# Main_Power.net
KiCad netlist of a schematic drawn in Altium Designer
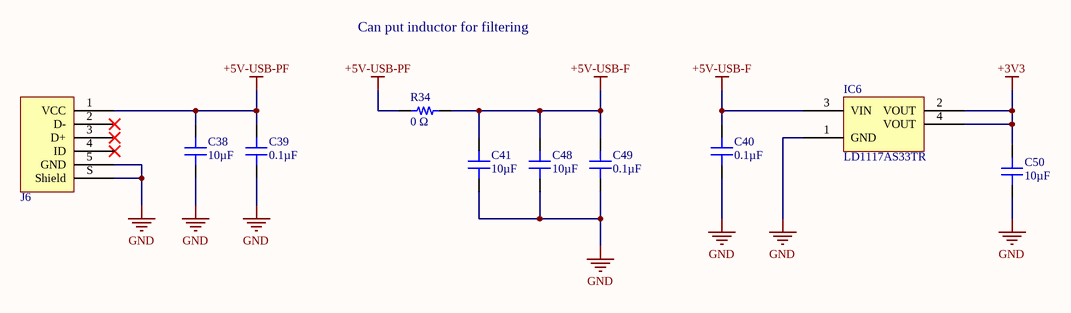
[diagram p0: Main Power.SchDoc]

(export (version "E")
  (design (tool "Eeschema 10.0.6"))
  (components
    (comp (ref "C38")
      (value "10µF")
      (footprint "CAP 0805_2012")
      (description "CAP CER 10UF 6.3V X5R 0805")
      (fields (field (name "PART NUMBER") "08056D106KAT4A") (field (name "MANUFACTURER") "AVX Corporation"))
      (libsource (lib "Generic Altium Database") (part "Capacitor"))
    )
    (comp (ref "C39")
      (value "0.1µF")
      (footprint "CAP 0402_1005")
      (description "CAP CER 0.1UF 6.3V X7R 0402")
      (fields
        (field (name "PART NUMBER") "0402B104K6R3CT")
        (field (name "MANUFACTURER") "Walsin Technology Corporation")
      )
      (libsource (lib "Generic Altium Database") (part "Capacitor"))
    )
    (comp (ref "C40")
      (value "0.1µF")
      (footprint "CAP 0402_1005")
      (description "CAP CER 0.1UF 6.3V X7R 0402")
      (fields
        (field (name "PART NUMBER") "0402B104K6R3CT")
        (field (name "MANUFACTURER") "Walsin Technology Corporation")
      )
      (libsource (lib "Generic Altium Database") (part "Capacitor"))
    )
    (comp (ref "C41")
      (value "10µF")
      (footprint "CAP 0805_2012")
      (description "CAP CER 10UF 6.3V X5R 0805")
      (fields (field (name "PART NUMBER") "08056D106KAT4A") (field (name "MANUFACTURER") "AVX Corporation"))
      (libsource (lib "Generic Altium Database") (part "Capacitor"))
    )
    (comp (ref "C48")
      (value "10µF")
      (footprint "CAP 0805_2012")
      (description "CAP CER 10UF 6.3V X5R 0805")
      (fields (field (name "PART NUMBER") "08056D106KAT4A") (field (name "MANUFACTURER") "AVX Corporation"))
      (libsource (lib "Generic Altium Database") (part "Capacitor"))
    )
    (comp (ref "C49")
      (value "0.1µF")
      (footprint "CAP 0402_1005")
      (description "CAP CER 0.1UF 6.3V X7R 0402")
      (fields
        (field (name "PART NUMBER") "0402B104K6R3CT")
        (field (name "MANUFACTURER") "Walsin Technology Corporation")
      )
      (libsource (lib "Generic Altium Database") (part "Capacitor"))
    )
    (comp (ref "C50")
      (value "10µF")
      (footprint "CAP 0805_2012")
      (description "CAP CER 10UF 6.3V X5R 0805")
      (fields (field (name "PART NUMBER") "08056D106KAT4A") (field (name "MANUFACTURER") "AVX Corporation"))
      (libsource (lib "Generic Altium Database") (part "Capacitor"))
    )
    (comp (ref "IC6")
      (value "LD1117AS33TR")
      (footprint "ST SOT-223")
      (description "IC REG LINEAR 3.3V 1A SOT223")
      (fields (field (name "MANUFACTURER") "STMicroelectronics"))
      (libsource (lib "Generic Altium Database") (part "ST LD1117"))
    )
    (comp (ref "J6")
      (value "10118193-0001LF")
      (footprint "FCI USB 10118193-0001LF")
      (description "CONN RCPT USB2.0 MICRO B SMD R/A")
      (fields (field (name "MANUFACTURER") "Amphenol ICC (FCI)"))
      (libsource (lib "Generic Altium Database") (part "USB 2.0 Type B Micro"))
    )
    (comp (ref "R34")
      (value "0 Ω")
      (footprint "RES 0805_2012")
      (description "RESA-AS 0805 0R JUMPER 125MW")
      (fields (field (name "PART NUMBER") "CR0805AJ/-000EAS") (field (name "MANUFACTURER") "Bourns Inc."))
      (libsource (lib "Generic Altium Database") (part "Resistor"))
    )
  )
  (nets
    (net (code "1") (name "+3V3") (class "Default")
      (node (ref "C50") (pin "2") (pinfunction "2_2") (pintype "passive"))
      (node (ref "IC6") (pin "2") (pinfunction "VOUT_2") (pintype "passive"))
      (node (ref "IC6") (pin "4") (pinfunction "VOUT_4") (pintype "passive"))
    )
    (net (code "2") (name "+5V-USB-F") (class "Default")
      (node (ref "C40") (pin "2") (pinfunction "2_2") (pintype "passive"))
      (node (ref "C41") (pin "2") (pinfunction "2_2") (pintype "passive"))
      (node (ref "C48") (pin "2") (pinfunction "2_2") (pintype "passive"))
      (node (ref "C49") (pin "2") (pinfunction "2_2") (pintype "passive"))
      (node (ref "IC6") (pin "3") (pinfunction "VIN_3") (pintype "passive"))
      (node (ref "R34") (pin "1") (pinfunction "1_1") (pintype "passive"))
    )
    (net (code "3") (name "+5V-USB-PF") (class "Default")
      (node (ref "C38") (pin "2") (pinfunction "2_2") (pintype "passive"))
      (node (ref "C39") (pin "2") (pinfunction "2_2") (pintype "passive"))
      (node (ref "J6") (pin "1") (pinfunction "VCC_1") (pintype "passive"))
      (node (ref "R34") (pin "2") (pinfunction "2_2") (pintype "passive"))
    )
    (net (code "4") (name "GND") (class "Default")
      (node (ref "C38") (pin "1") (pinfunction "1_1") (pintype "passive"))
      (node (ref "C39") (pin "1") (pinfunction "1_1") (pintype "passive"))
      (node (ref "C40") (pin "1") (pinfunction "1_1") (pintype "passive"))
      (node (ref "C41") (pin "1") (pinfunction "1_1") (pintype "passive"))
      (node (ref "C48") (pin "1") (pinfunction "1_1") (pintype "passive"))
      (node (ref "C49") (pin "1") (pinfunction "1_1") (pintype "passive"))
      (node (ref "C50") (pin "1") (pinfunction "1_1") (pintype "passive"))
      (node (ref "IC6") (pin "1") (pinfunction "GND_1") (pintype "passive"))
      (node (ref "J6") (pin "5") (pinfunction "GND_5") (pintype "passive"))
      (node (ref "J6") (pin "S") (pinfunction "Shield_S") (pintype "passive"))
    )
    (net (code "5") (name "unconnected-(J6-D+-Pad3)") (class "Default")
      (node (ref "J6") (pin "3") (pinfunction "D+_3") (pintype "passive+no_connect"))
    )
    (net (code "6") (name "unconnected-(J6-D--Pad2)") (class "Default")
      (node (ref "J6") (pin "2") (pinfunction "D-_2") (pintype "passive+no_connect"))
    )
    (net (code "7") (name "unconnected-(J6-ID-Pad4)") (class "Default")
      (node (ref "J6") (pin "4") (pinfunction "ID_4") (pintype "passive+no_connect"))
    )
  )
)
